# gyro.net
KiCad netlist of a schematic drawn in EAGLE
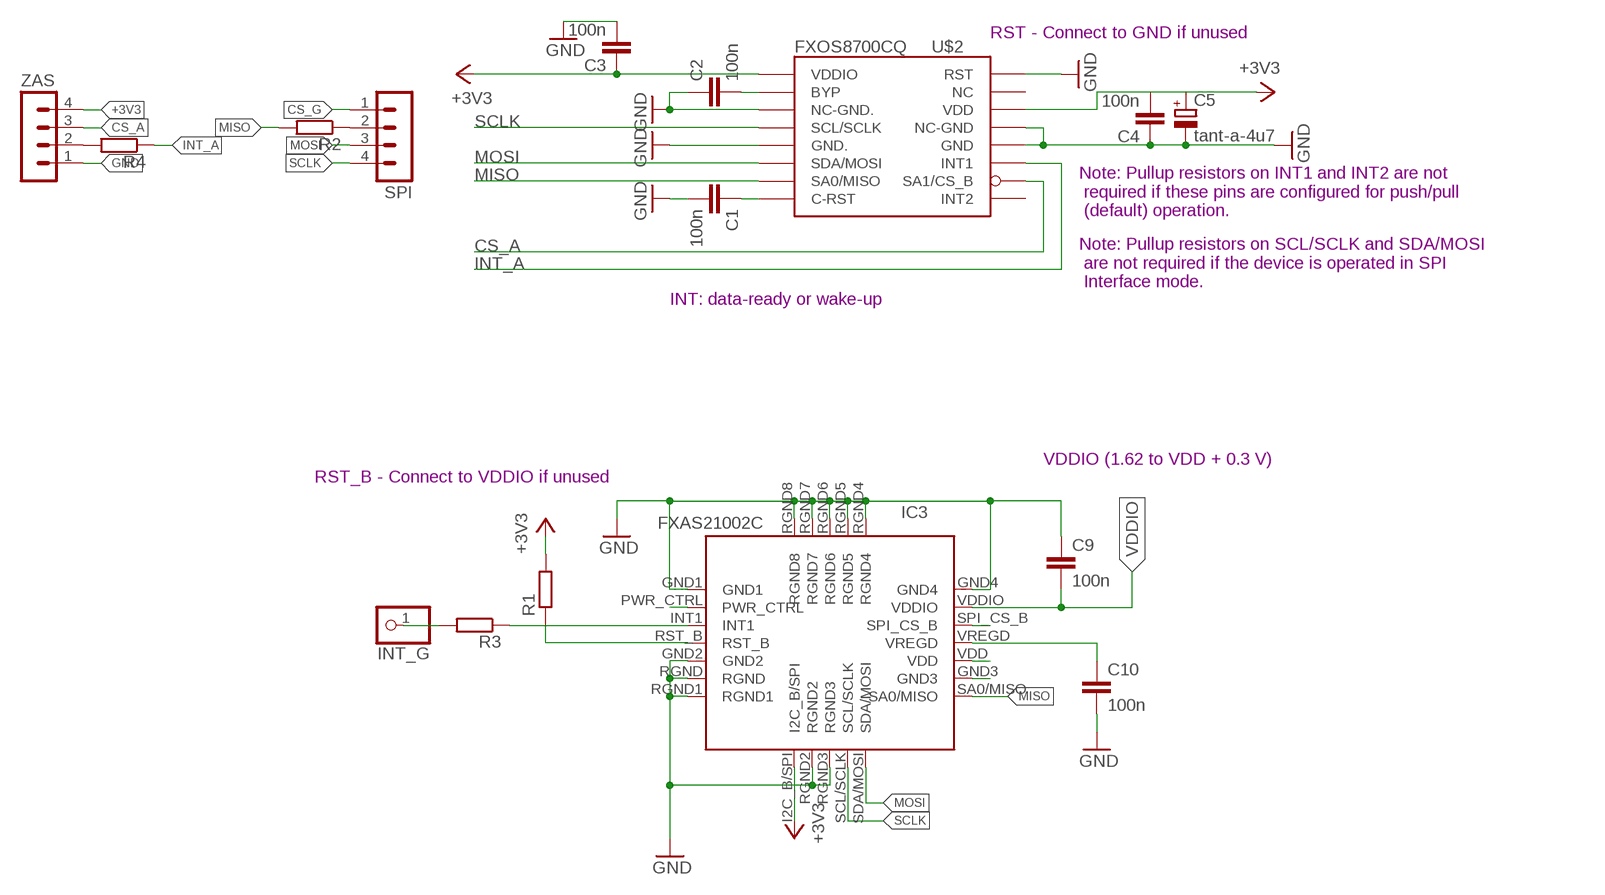
[diagram p0: schematic, sheet 1]

(export (version "E")
  (design (tool "Eeschema 10.0.6"))
  (components
    (comp (ref "C1")
      (value "100n")
      (footprint "eagle-import:C0603")
      (libsource (lib "eagle-import") (part "C-EUC0603"))
    )
    (comp (ref "C2")
      (value "100n")
      (footprint "eagle-import:C0603")
      (libsource (lib "eagle-import") (part "C-EUC0603"))
    )
    (comp (ref "C3")
      (value "100n")
      (footprint "eagle-import:C0603")
      (libsource (lib "eagle-import") (part "C-EUC0603"))
    )
    (comp (ref "C4")
      (value "100n")
      (footprint "eagle-import:C0603")
      (libsource (lib "eagle-import") (part "C-EUC0603"))
    )
    (comp (ref "C5")
      (value "tant-a-4u7")
      (footprint "eagle-import:SMC_A")
      (libsource (lib "eagle-import") (part "CPOL-EUSMCA"))
    )
    (comp (ref "C9")
      (value "100n")
      (footprint "eagle-import:C0603")
      (libsource (lib "eagle-import") (part "C-EUC0603"))
    )
    (comp (ref "C10")
      (value "100n")
      (footprint "eagle-import:C0603")
      (libsource (lib "eagle-import") (part "C-EUC0603"))
    )
    (comp (ref "IC3")
      (value "FXAS21002C")
      (footprint "eagle-import:QFN24-4X4")
      (libsource (lib "eagle-import") (part "FXAS21002C"))
    )
    (comp (ref "INT_G")
      (value "PINHD-1X1")
      (footprint "eagle-import:1X01")
      (libsource (lib "eagle-import") (part "PINHD-1X1"))
    )
    (comp (ref "R1")
      (value "R-EU_R0603")
      (footprint "eagle-import:R0603")
      (libsource (lib "eagle-import") (part "R-EU_R0603"))
    )
    (comp (ref "R2")
      (value "R-EU_R0603")
      (footprint "eagle-import:R0603")
      (libsource (lib "eagle-import") (part "R-EU_R0603"))
    )
    (comp (ref "R3")
      (value "R-EU_R0603")
      (footprint "eagle-import:R0603")
      (libsource (lib "eagle-import") (part "R-EU_R0603"))
    )
    (comp (ref "R4")
      (value "R-EU_R0603")
      (footprint "eagle-import:R0603")
      (libsource (lib "eagle-import") (part "R-EU_R0603"))
    )
    (comp (ref "SPI")
      (value "MA04-1")
      (footprint "eagle-import:MA04-1")
      (libsource (lib "eagle-import") (part "MA04-1"))
    )
    (comp (ref "U$2")
      (value "FXOS8700CQR1")
      (footprint "eagle-import:QFN16-5X3")
      (libsource (lib "eagle-import") (part "FXOS8700CQR1"))
    )
    (comp (ref "ZAS")
      (value "MA04-1")
      (footprint "eagle-import:MA04-1")
      (libsource (lib "eagle-import") (part "MA04-1"))
    )
  )
  (nets
    (net (code "1") (name "+3V3") (class "Default")
      (node (ref "C3") (pin "1") (pinfunction "1_1") (pintype "passive"))
      (node (ref "C4") (pin "2") (pinfunction "2_2") (pintype "passive"))
      (node (ref "C5") (pin "+") (pinfunction "+_+") (pintype "passive"))
      (node (ref "IC3") (pin "I2C_B/SPI") (pinfunction "I2C_B/SPI_I2C_B/SPI") (pintype "bidirectional"))
      (node (ref "IC3") (pin "VDD") (pinfunction "VDD_VDD") (pintype "bidirectional"))
      (node (ref "R1") (pin "2") (pinfunction "2_2") (pintype "passive"))
      (node (ref "U$2") (pin "P$1") (pinfunction "VDDIO_P$1") (pintype "power_in"))
      (node (ref "U$2") (pin "P$14") (pinfunction "VDD_P$14") (pintype "power_in"))
      (node (ref "ZAS") (pin "4") (pinfunction "4_4") (pintype "passive"))
    )
    (net (code "2") (name "CS_A") (class "Default")
      (node (ref "U$2") (pin "P$10") (pinfunction "SA1/CS_B_P$10") (pintype "input"))
      (node (ref "ZAS") (pin "3") (pinfunction "3_3") (pintype "passive"))
    )
    (net (code "3") (name "CS_G") (class "Default")
      (node (ref "IC3") (pin "SPI_CS_B") (pinfunction "SPI_CS_B_SPI_CS_B") (pintype "bidirectional"))
      (node (ref "SPI") (pin "1") (pinfunction "1_1") (pintype "passive"))
    )
    (net (code "4") (name "GND") (class "Default")
      (node (ref "C1") (pin "2") (pinfunction "2_2") (pintype "passive"))
      (node (ref "C10") (pin "2") (pinfunction "2_2") (pintype "passive"))
      (node (ref "C2") (pin "1") (pinfunction "1_1") (pintype "passive"))
      (node (ref "C3") (pin "2") (pinfunction "2_2") (pintype "passive"))
      (node (ref "C4") (pin "1") (pinfunction "1_1") (pintype "passive"))
      (node (ref "C5") (pin "-") (pinfunction "-_-") (pintype "passive"))
      (node (ref "C9") (pin "1") (pinfunction "1_1") (pintype "passive"))
      (node (ref "IC3") (pin "GND1") (pinfunction "GND1_GND1") (pintype "bidirectional"))
      (node (ref "IC3") (pin "GND2") (pinfunction "GND2_GND2") (pintype "bidirectional"))
      (node (ref "IC3") (pin "GND3") (pinfunction "GND3_GND3") (pintype "bidirectional"))
      (node (ref "IC3") (pin "GND4") (pinfunction "GND4_GND4") (pintype "bidirectional"))
      (node (ref "IC3") (pin "RGND") (pinfunction "RGND_RGND") (pintype "bidirectional"))
      (node (ref "IC3") (pin "RGND1") (pinfunction "RGND1_RGND1") (pintype "bidirectional"))
      (node (ref "IC3") (pin "RGND2") (pinfunction "RGND2_RGND2") (pintype "bidirectional"))
      (node (ref "IC3") (pin "RGND3") (pinfunction "RGND3_RGND3") (pintype "bidirectional"))
      (node (ref "IC3") (pin "RGND4") (pinfunction "RGND4_RGND4") (pintype "bidirectional"))
      (node (ref "IC3") (pin "RGND5") (pinfunction "RGND5_RGND5") (pintype "bidirectional"))
      (node (ref "IC3") (pin "RGND6") (pinfunction "RGND6_RGND6") (pintype "bidirectional"))
      (node (ref "IC3") (pin "RGND7") (pinfunction "RGND7_RGND7") (pintype "bidirectional"))
      (node (ref "IC3") (pin "RGND8") (pinfunction "RGND8_RGND8") (pintype "bidirectional"))
      (node (ref "U$2") (pin "P$12") (pinfunction "GND_P$12") (pintype "power_in"))
      (node (ref "U$2") (pin "P$13") (pinfunction "NC-GND_P$13") (pintype "input"))
      (node (ref "U$2") (pin "P$16") (pinfunction "RST_P$16") (pintype "input"))
      (node (ref "U$2") (pin "P$3") (pinfunction "NC-GND._P$3") (pintype "input"))
      (node (ref "U$2") (pin "P$5") (pinfunction "GND._P$5") (pintype "power_in"))
      (node (ref "ZAS") (pin "1") (pinfunction "1_1") (pintype "passive"))
    )
    (net (code "5") (name "INT_A") (class "Default")
      (node (ref "R4") (pin "1") (pinfunction "1_1") (pintype "passive"))
      (node (ref "U$2") (pin "P$11") (pinfunction "INT1_P$11") (pintype "output"))
    )
    (net (code "6") (name "MISO") (class "Default")
      (node (ref "IC3") (pin "SA0/MISO") (pinfunction "SA0/MISO_SA0/MISO") (pintype "bidirectional"))
      (node (ref "R2") (pin "2") (pinfunction "2_2") (pintype "passive"))
      (node (ref "U$2") (pin "P$7") (pinfunction "SA0/MISO_P$7") (pintype "output"))
    )
    (net (code "7") (name "MOSI") (class "Default")
      (node (ref "IC3") (pin "SDA/MOSI") (pinfunction "SDA/MOSI_SDA/MOSI") (pintype "bidirectional"))
      (node (ref "SPI") (pin "3") (pinfunction "3_3") (pintype "passive"))
      (node (ref "U$2") (pin "P$6") (pinfunction "SDA/MOSI_P$6") (pintype "input"))
    )
    (net (code "8") (name "Net-(C10-Pad1)") (class "Default")
      (node (ref "C10") (pin "1") (pinfunction "1_1") (pintype "passive"))
      (node (ref "IC3") (pin "VREGD") (pinfunction "VREGD_VREGD") (pintype "bidirectional"))
    )
    (net (code "9") (name "Net-(IC3-PadINT1)") (class "Default")
      (node (ref "IC3") (pin "INT1") (pinfunction "INT1_INT1") (pintype "bidirectional"))
      (node (ref "R3") (pin "1") (pinfunction "1_1") (pintype "passive"))
    )
    (net (code "10") (name "Net-(IC3-PadRST_B)") (class "Default")
      (node (ref "IC3") (pin "RST_B") (pinfunction "RST_B_RST_B") (pintype "bidirectional"))
      (node (ref "R1") (pin "1") (pinfunction "1_1") (pintype "passive"))
    )
    (net (code "11") (name "Net-(INT_G-Pad1)") (class "Default")
      (node (ref "INT_G") (pin "1") (pinfunction "1_1") (pintype "passive"))
      (node (ref "R3") (pin "2") (pinfunction "2_2") (pintype "passive"))
    )
    (net (code "12") (name "Net-(R2-Pad1)") (class "Default")
      (node (ref "R2") (pin "1") (pinfunction "1_1") (pintype "passive"))
      (node (ref "SPI") (pin "2") (pinfunction "2_2") (pintype "passive"))
    )
    (net (code "13") (name "Net-(R4-Pad2)") (class "Default")
      (node (ref "R4") (pin "2") (pinfunction "2_2") (pintype "passive"))
      (node (ref "ZAS") (pin "2") (pinfunction "2_2") (pintype "passive"))
    )
    (net (code "14") (name "Net-(U$2-BYP)") (class "Default")
      (node (ref "C2") (pin "2") (pinfunction "2_2") (pintype "passive"))
      (node (ref "U$2") (pin "P$2") (pinfunction "BYP_P$2") (pintype "bidirectional"))
    )
    (net (code "15") (name "Net-(U$2-C-RST)") (class "Default")
      (node (ref "C1") (pin "1") (pinfunction "1_1") (pintype "passive"))
      (node (ref "U$2") (pin "P$8") (pinfunction "C-RST_P$8") (pintype "bidirectional"))
    )
    (net (code "16") (name "SCLK") (class "Default")
      (node (ref "IC3") (pin "SCL/SCLK") (pinfunction "SCL/SCLK_SCL/SCLK") (pintype "bidirectional"))
      (node (ref "SPI") (pin "4") (pinfunction "4_4") (pintype "passive"))
      (node (ref "U$2") (pin "P$4") (pinfunction "SCL/SCLK_P$4") (pintype "input"))
    )
    (net (code "17") (name "VDDIO") (class "Default")
      (node (ref "C9") (pin "2") (pinfunction "2_2") (pintype "passive"))
      (node (ref "IC3") (pin "VDDIO") (pinfunction "VDDIO_VDDIO") (pintype "bidirectional"))
    )
    (net (code "18") (name "unconnected-(IC3-PadPWR_CTRL)") (class "Default")
      (node (ref "IC3") (pin "PWR_CTRL") (pinfunction "PWR_CTRL_PWR_CTRL") (pintype "bidirectional"))
    )
    (net (code "19") (name "unconnected-(U$2-INT2-PadP$9)") (class "Default")
      (node (ref "U$2") (pin "P$9") (pinfunction "INT2_P$9") (pintype "output"))
    )
    (net (code "20") (name "unconnected-(U$2-NC-PadP$15)") (class "Default")
      (node (ref "U$2") (pin "P$15") (pinfunction "NC_P$15") (pintype "no_connect"))
    )
  )
)
